# HighPassFilter.net
KiCad netlist of a schematic drawn in Altium Designer
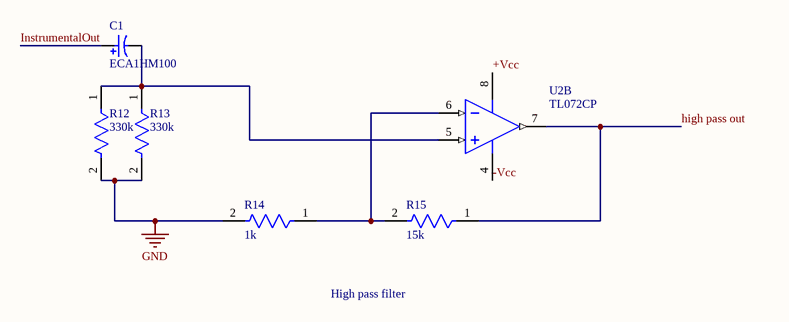
[diagram p0: HighPassFilter.SchDoc]

(export (version "E")
  (design (tool "Eeschema 10.0.6"))
  (components
    (comp (ref "C1")
      (value "ECA1HM100")
      (footprint "CAPPR55-200-1100X500X1200")
      (description "Aluminum Electrolytic Capacitor, 10 uF, +/- 20%, 50 V, -40 to 85 degC, 2-Pin THD, RoHS, Bulk")
      (fields (field (name "MANUFACTURER") "Panasonic") (field (name "TOLERANCE") "20%"))
      (libsource (lib "Altium Content Vault") (part "CAP-P-2"))
    )
    (comp (ref "R12")
      (value "330k")
      (footprint "FP-CFR-25-MFG")
      (description "RES 10 OHM 1/4W 5% AXIAL")
      (fields (field (name "TOLERANCE") "5%"))
      (libsource (lib "Altium Content Vault") (part "1029c3af85768c4190bb7ad29bc67b5"))
    )
    (comp (ref "R13")
      (value "330k")
      (footprint "FP-CFR-25-MFG")
      (description "RES 10 OHM 1/4W 5% AXIAL")
      (fields (field (name "TOLERANCE") "5%"))
      (libsource (lib "Altium Content Vault") (part "1029c3af85768c4190bb7ad29bc67b5"))
    )
    (comp (ref "R14")
      (value "1k")
      (footprint "FP-CFR-25-MFG")
      (description "RES 10 OHM 1/4W 5% AXIAL")
      (fields (field (name "TOLERANCE") "5%"))
      (libsource (lib "Altium Content Vault") (part "1029c3af85768c4190bb7ad29bc67b5"))
    )
    (comp (ref "R15")
      (value "15k")
      (footprint "FP-CFR-25-MFG")
      (description "RES 10 OHM 1/4W 5% AXIAL")
      (fields (field (name "TOLERANCE") "5%"))
      (libsource (lib "Altium Content Vault") (part "1029c3af85768c4190bb7ad29bc67b5"))
    )
    (comp (ref "U2")
      (value "TL072CP")
      (footprint "P0008A")
      (fields (field (name "MANUFACTURER") "Texas Instruments"))
      (libsource (lib "Altium Content Vault") (part "TI-AMP-D6-2-8_D"))
    )
  )
  (nets
    (net (code "1") (name "/+Vcc") (class "Default")
      (node (ref "U2") (pin "8") (pinfunction "VCC+_8") (pintype "power_in"))
    )
    (net (code "2") (name "/-Vcc") (class "Default")
      (node (ref "U2") (pin "4") (pinfunction "VCC-_4") (pintype "power_in"))
    )
    (net (code "3") (name "/InstrumentalOut") (class "Default")
      (node (ref "C1") (pin "1") (pinfunction "1_1") (pintype "passive"))
    )
    (net (code "4") (name "/high pass out") (class "Default")
      (node (ref "R15") (pin "1") (pinfunction "1_1") (pintype "passive"))
      (node (ref "U2") (pin "7") (pinfunction "OUT2_7") (pintype "output"))
    )
    (net (code "5") (name "GND") (class "Default")
      (node (ref "R12") (pin "2") (pinfunction "2_2") (pintype "passive"))
      (node (ref "R13") (pin "2") (pinfunction "2_2") (pintype "passive"))
      (node (ref "R14") (pin "2") (pinfunction "2_2") (pintype "passive"))
    )
    (net (code "6") (name "Net-(U2B-IN2+)") (class "Default")
      (node (ref "C1") (pin "2") (pinfunction "2_2") (pintype "passive"))
      (node (ref "R12") (pin "1") (pinfunction "1_1") (pintype "passive"))
      (node (ref "R13") (pin "1") (pinfunction "1_1") (pintype "passive"))
      (node (ref "U2") (pin "5") (pinfunction "IN2+_5") (pintype "input"))
    )
    (net (code "7") (name "Net-(U2B-IN2-)") (class "Default")
      (node (ref "R14") (pin "1") (pinfunction "1_1") (pintype "passive"))
      (node (ref "R15") (pin "2") (pinfunction "2_2") (pintype "passive"))
      (node (ref "U2") (pin "6") (pinfunction "IN2-_6") (pintype "input"))
    )
  )
)
